# Power.net
KiCad netlist of a schematic drawn in Altium Designer
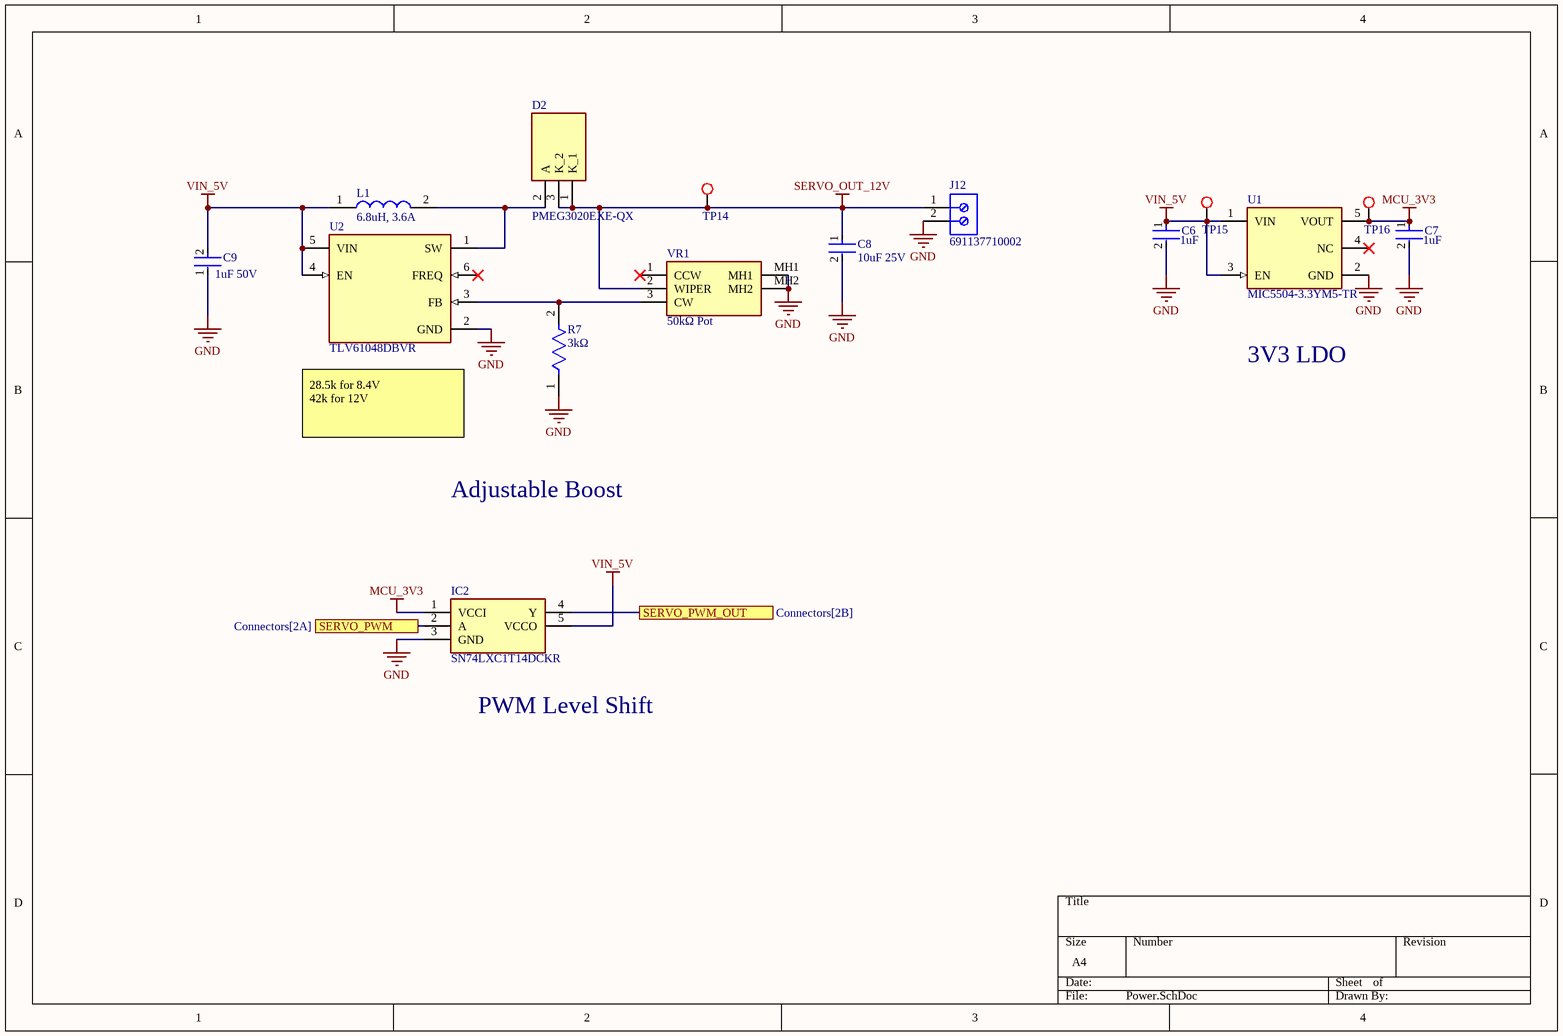
[diagram p0: Power.SchDoc]

(export (version "E")
  (design (tool "Eeschema 10.0.6"))
  (components
    (comp (ref "C6")
      (value "1uF")
      (footprint "FP-CL10-IPC_C")
      (description "Cap Ceramic 1uF 10V X5R ±10% Pad SMD 0603 +85°C T/R")
      (fields (field (name "VOLTAGE") "10V") (field (name "TOLERANCE") "10%"))
      (libsource (lib "Altium Content Vault") (part "b4654b650e69147ec39a6b967a45e02"))
    )
    (comp (ref "C7")
      (value "1uF")
      (footprint "FP-CL10-IPC_C")
      (description "Cap Ceramic 1uF 10V X5R ±10% Pad SMD 0603 +85°C T/R")
      (fields (field (name "VOLTAGE") "10V") (field (name "TOLERANCE") "10%"))
      (libsource (lib "Altium Content Vault") (part "b4654b650e69147ec39a6b967a45e02"))
    )
    (comp (ref "C8")
      (value "10uF 25V")
      (footprint "FP-CL31-IPC_B")
      (description "Cap Ceramic 10uF 25V X7R ±10% SMD 1206 +125°C Embossed T/R")
      (fields (field (name "TOLERANCE") "10%"))
      (libsource (lib "Altium Content Vault") (part "b4654b650e69147ec39a6b967a45e02"))
    )
    (comp (ref "C9")
      (value "1uF 50V")
      (footprint "FP-C1608-080-0_1-IPC_B")
      (description "Multilayer Ceramic Capacitors 1μF ±10% 50V X5R SMD 0603")
      (fields (field (name "VOLTAGE") "50V") (field (name "TOLERANCE") "10%"))
      (libsource (lib "Altium Content Vault") (part "236180d848d6139a670b325ea6854c9"))
    )
    (comp (ref "D2")
      (value "PMEG3020EXE-QX")
      (footprint "SamacSys:PMEG4010EXEX")
      (description "Schottky Diode")
      (fields (field (name "MOUSER PART NUMBER") "771-PMEG3020EXE-Q"))
      (libsource (lib "*") (part "PMEG3020EXE-QX"))
    )
    (comp (ref "IC2")
      (value "SN74LXC1T14DCKR")
      (footprint "SamacSys:SOT65P210X110-5N")
      (description "Integrated Circuit")
      (fields (field (name "MOUSER PART NUMBER") "595-SN74LXC1T14DCKR"))
      (libsource (lib "*") (part "SN74LXC1T14DCKR"))
    )
    (comp (ref "J12")
      (value "691137710002")
      (footprint "691137710002")
      (libsource (lib "Altium Content Vault") (part "TBL - 1R - 02P - Screw"))
    )
    (comp (ref "L1")
      (value "6.8uH, 3.6A")
      (footprint "SamacSys:VLS6045")
      (description "Inductor")
      (fields
        (field (name "MANUFACTURER_PART_NUMBER") "VLS6045EX-6R8M")
        (field (name "MOUSER PART NUMBER") "810-VLS6045EX-6R8M")
      )
      (libsource (lib "*") (part "VLS6045EX-6R8M"))
    )
    (comp (ref "R7")
      (value "3kΩ")
      (footprint "FP-RG2012-IPC_A")
      (description "Automotive Metal Thin Film Chip Resistor, 0805, 3kΩ, 0.1%, 25ppm/°C, 0.125W, 150V")
      (fields (field (name "TOLERANCE") "0.1%"))
      (libsource (lib "Altium Content Vault") (part "1029c3af85768c4190bb7ad29bc67b5"))
    )
    (comp (ref "TP14") (value "TP") (footprint "Testpoint") (libsource (lib "Schlib1") (part "Testpoint")))
    (comp (ref "TP15") (value "TP") (footprint "Testpoint") (libsource (lib "Schlib1") (part "Testpoint")))
    (comp (ref "TP16") (value "TP") (footprint "Testpoint") (libsource (lib "Schlib1") (part "Testpoint")))
    (comp (ref "U1")
      (value "MIC5504-3.3YM5-TR")
      (footprint "FP-SOT23-5LD-PL-1-MFG")
      (description "IC REG LINEAR 3.3V 300MA SOT23-5")
      (libsource (lib "Altium Content Vault") (part "96048095611b4a9579e1e315950d302"))
    )
    (comp (ref "U2")
      (value "TLV61048DBVR")
      (footprint "FP-DBV0006A-IPC_B")
      (description "IC REG BOOST ADJ SOT23-6")
      (libsource (lib "Altium Content Vault") (part "6b380b3b858d595bad87464c0f74cb2"))
    )
    (comp (ref "VR1")
      (value "50kΩ Pot")
      (footprint "SamacSys:PTV09A4030SA503")
      (description "Variable Resistor")
      (fields
        (field (name "MANUFACTURER_PART_NUMBER") "PTV09A-4030S-A503")
        (field (name "MOUSER PART NUMBER") "652-PTV09A-4030SA503")
      )
      (libsource (lib "*") (part "PTV09A-4030S-A503"))
    )
  )
  (nets
    (net (code "1") (name "/SERVO_PWM") (class "Default")
      (node (ref "IC2") (pin "2") (pinfunction "A_2") (pintype "passive"))
    )
    (net (code "2") (name "/SERVO_PWM_OUT") (class "Default")
      (node (ref "IC2") (pin "4") (pinfunction "Y_4") (pintype "passive"))
    )
    (net (code "3") (name "GND") (class "Default")
      (node (ref "C6") (pin "2") (pinfunction "2_2") (pintype "passive"))
      (node (ref "C7") (pin "2") (pinfunction "2_2") (pintype "passive"))
      (node (ref "C8") (pin "2") (pinfunction "2_2") (pintype "passive"))
      (node (ref "C9") (pin "1") (pinfunction "1_1") (pintype "passive"))
      (node (ref "IC2") (pin "3") (pinfunction "GND_3") (pintype "passive"))
      (node (ref "J12") (pin "2") (pinfunction "2_2") (pintype "passive"))
      (node (ref "R7") (pin "1") (pinfunction "1_1") (pintype "passive"))
      (node (ref "U1") (pin "2") (pinfunction "GND_2") (pintype "power_in"))
      (node (ref "U2") (pin "2") (pinfunction "GND_2") (pintype "power_in"))
      (node (ref "VR1") (pin "MH1") (pinfunction "MH1_MH1") (pintype "passive"))
      (node (ref "VR1") (pin "MH2") (pinfunction "MH2_MH2") (pintype "passive"))
    )
    (net (code "4") (name "MCU_3V3") (class "Default")
      (node (ref "C7") (pin "1") (pinfunction "1_1") (pintype "passive"))
      (node (ref "IC2") (pin "1") (pinfunction "VCCI_1") (pintype "passive"))
      (node (ref "TP16") (pin "0") (pinfunction "0_0") (pintype "passive"))
      (node (ref "U1") (pin "5") (pinfunction "VOUT_5") (pintype "power_in"))
    )
    (net (code "5") (name "Net-(D2-A)") (class "Default")
      (node (ref "D2") (pin "2") (pinfunction "A_2") (pintype "passive"))
      (node (ref "L1") (pin "2") (pinfunction "2_2") (pintype "passive"))
      (node (ref "U2") (pin "1") (pinfunction "SW_1") (pintype "power_in"))
    )
    (net (code "6") (name "Net-(U2-FB)") (class "Default")
      (node (ref "R7") (pin "2") (pinfunction "2_2") (pintype "passive"))
      (node (ref "U2") (pin "3") (pinfunction "FB_3") (pintype "input"))
      (node (ref "VR1") (pin "3") (pinfunction "CW_3") (pintype "passive"))
    )
    (net (code "7") (name "SERVO_OUT_12V") (class "Default")
      (node (ref "C8") (pin "1") (pinfunction "1_1") (pintype "passive"))
      (node (ref "D2") (pin "1") (pinfunction "K_1_1") (pintype "passive"))
      (node (ref "D2") (pin "3") (pinfunction "K_2_3") (pintype "passive"))
      (node (ref "J12") (pin "1") (pinfunction "1_1") (pintype "passive"))
      (node (ref "TP14") (pin "0") (pinfunction "0_0") (pintype "passive"))
      (node (ref "VR1") (pin "2") (pinfunction "WIPER_2") (pintype "passive"))
    )
    (net (code "8") (name "VIN_5V") (class "Default")
      (node (ref "C6") (pin "1") (pinfunction "1_1") (pintype "passive"))
      (node (ref "C9") (pin "2") (pinfunction "2_2") (pintype "passive"))
      (node (ref "IC2") (pin "5") (pinfunction "VCCO_5") (pintype "passive"))
      (node (ref "L1") (pin "1") (pinfunction "1_1") (pintype "passive"))
      (node (ref "TP15") (pin "0") (pinfunction "0_0") (pintype "passive"))
      (node (ref "U1") (pin "1") (pinfunction "VIN_1") (pintype "power_in"))
      (node (ref "U1") (pin "3") (pinfunction "EN_3") (pintype "input"))
      (node (ref "U2") (pin "4") (pinfunction "EN_4") (pintype "input"))
      (node (ref "U2") (pin "5") (pinfunction "VIN_5") (pintype "power_in"))
    )
    (net (code "9") (name "unconnected-(U1-NC-Pad4)") (class "Default")
      (node (ref "U1") (pin "4") (pinfunction "NC_4") (pintype "passive+no_connect"))
    )
    (net (code "10") (name "unconnected-(U2-FREQ-Pad6)") (class "Default")
      (node (ref "U2") (pin "6") (pinfunction "FREQ_6") (pintype "input+no_connect"))
    )
    (net (code "11") (name "unconnected-(VR1-CCW-Pad1)") (class "Default")
      (node (ref "VR1") (pin "1") (pinfunction "CCW_1") (pintype "passive+no_connect"))
    )
  )
)
